# h2oiq_v4_long.net
KiCad netlist of a schematic drawn in EAGLE
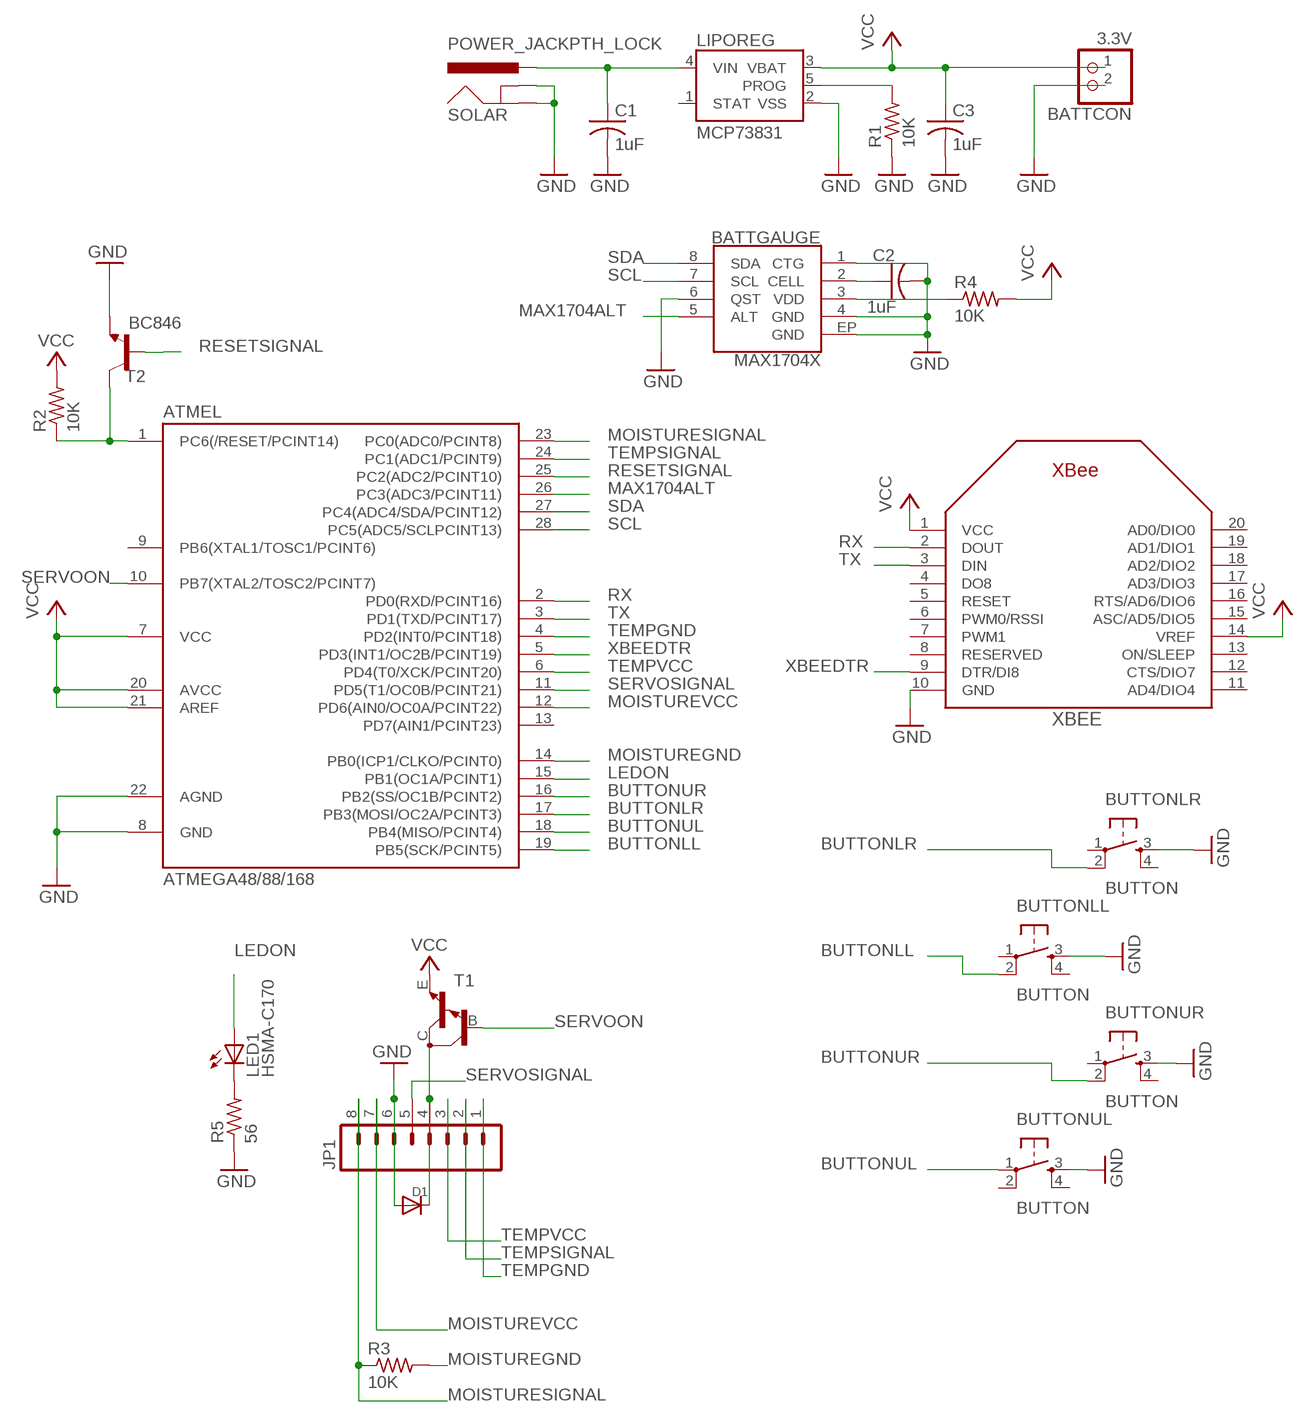
[diagram p0: schematic, sheet 1]

(export (version "E")
  (design (tool "Eeschema 10.0.6"))
  (components
    (comp (ref "ATMEL")
      (value "ATMEGA48/88/168")
      (footprint "eagle-import:DIL28-3")
      (libsource (lib "eagle-import") (part "MEGA48/88/168-PU"))
    )
    (comp (ref "BATTCON")
      (value "3.3V")
      (footprint "eagle-import:JST-PH-2-THM")
      (libsource (lib "eagle-import") (part "JST_2PIN-THM"))
    )
    (comp (ref "BATTGAUGE")
      (value "MAX1704X")
      (footprint "eagle-import:TDFN-8")
      (libsource (lib "eagle-import") (part "MAX1704X"))
    )
    (comp (ref "BUTTONLL")
      (value "BUTTON")
      (footprint "eagle-import:TACTILE-PTH")
      (libsource (lib "eagle-import") (part "TAC_SWITCHPTH"))
    )
    (comp (ref "BUTTONLR")
      (value "BUTTON")
      (footprint "eagle-import:TACTILE-PTH")
      (libsource (lib "eagle-import") (part "TAC_SWITCHPTH"))
    )
    (comp (ref "BUTTONUL")
      (value "BUTTON")
      (footprint "eagle-import:TACTILE-PTH")
      (libsource (lib "eagle-import") (part "TAC_SWITCHPTH"))
    )
    (comp (ref "BUTTONUR")
      (value "BUTTON")
      (footprint "eagle-import:TACTILE-PTH")
      (libsource (lib "eagle-import") (part "TAC_SWITCHPTH"))
    )
    (comp (ref "C1")
      (value "1uF")
      (footprint "eagle-import:C0603K")
      (libsource (lib "eagle-import") (part "C-USC0603K"))
    )
    (comp (ref "C2")
      (value "1uF")
      (footprint "eagle-import:C0603K")
      (libsource (lib "eagle-import") (part "C-USC0603K"))
    )
    (comp (ref "C3")
      (value "1uF")
      (footprint "eagle-import:C0603K")
      (libsource (lib "eagle-import") (part "C-USC0603K"))
    )
    (comp (ref "D1")
      (value "DIODESMA")
      (footprint "eagle-import:SMADIODE")
      (libsource (lib "eagle-import") (part "DIODESMA"))
    )
    (comp (ref "JP1")
      (value "M081X08")
      (footprint "eagle-import:1X08")
      (libsource (lib "eagle-import") (part "M081X08"))
    )
    (comp (ref "LED1")
      (value "HSMA-C170")
      (footprint "eagle-import:SMARTLED-TTW")
      (libsource (lib "eagle-import") (part "LED"))
    )
    (comp (ref "LIPOREG")
      (value "MCP73831")
      (footprint "eagle-import:SOT23-5")
      (libsource (lib "eagle-import") (part "MCP73831"))
    )
    (comp (ref "R1")
      (value "10K")
      (footprint "eagle-import:R0805")
      (libsource (lib "eagle-import") (part "R-US_R0805"))
    )
    (comp (ref "R2")
      (value "10K")
      (footprint "eagle-import:R0805")
      (libsource (lib "eagle-import") (part "R-US_R0805"))
    )
    (comp (ref "R3")
      (value "10K")
      (footprint "eagle-import:R0805")
      (libsource (lib "eagle-import") (part "R-US_R0805"))
    )
    (comp (ref "R4")
      (value "10K")
      (footprint "eagle-import:R0805")
      (libsource (lib "eagle-import") (part "R-US_R0805"))
    )
    (comp (ref "R5")
      (value "56")
      (footprint "eagle-import:R0805")
      (libsource (lib "eagle-import") (part "R-US_R0805"))
    )
    (comp (ref "SOLAR")
      (value "POWER_JACKPTH_LOCK")
      (footprint "eagle-import:POWER_JACK_PTH_LOCK")
      (libsource (lib "eagle-import") (part "POWER_JACKPTH_LOCK"))
    )
    (comp (ref "T1")
      (value "MMBTA13LT1-NPN_DARL-SOT23-BEC")
      (footprint "eagle-import:SOT23-BEC")
      (libsource (lib "eagle-import") (part "-NPN_DARL-SOT23-BECMMBTA13LT1"))
    )
    (comp (ref "T2")
      (value "BC846")
      (footprint "eagle-import:SOT23")
      (libsource (lib "eagle-import") (part "BC846"))
    )
    (comp (ref "XBEE")
      (value "XBEE")
      (footprint "eagle-import:XBEE")
      (libsource (lib "eagle-import") (part "XBEE"))
    )
  )
  (nets
    (net (code "1") (name "/BUTTONLL") (class "Default")
      (node (ref "ATMEL") (pin "19") (pinfunction "PB5(SCK/PCINT5)_19") (pintype "bidirectional"))
      (node (ref "BUTTONLL") (pin "2") (pinfunction "2_2") (pintype "passive"))
    )
    (net (code "2") (name "/BUTTONLR") (class "Default")
      (node (ref "ATMEL") (pin "17") (pinfunction "PB3(MOSI/OC2A/PCINT3)_17") (pintype "bidirectional"))
      (node (ref "BUTTONLR") (pin "2") (pinfunction "2_2") (pintype "passive"))
    )
    (net (code "3") (name "/BUTTONUL") (class "Default")
      (node (ref "ATMEL") (pin "18") (pinfunction "PB4(MISO/PCINT4)_18") (pintype "bidirectional"))
      (node (ref "BUTTONUL") (pin "1") (pinfunction "1_1") (pintype "passive"))
    )
    (net (code "4") (name "/BUTTONUR") (class "Default")
      (node (ref "ATMEL") (pin "16") (pinfunction "PB2(SS/OC1B/PCINT2)_16") (pintype "bidirectional"))
      (node (ref "BUTTONUR") (pin "2") (pinfunction "2_2") (pintype "passive"))
    )
    (net (code "5") (name "/LEDON") (class "Default")
      (node (ref "ATMEL") (pin "15") (pinfunction "PB1(OC1A/PCINT1)_15") (pintype "bidirectional"))
      (node (ref "LED1") (pin "A@1") (pinfunction "A_A@1") (pintype "passive"))
    )
    (net (code "6") (name "/MAX1704ALT") (class "Default")
      (node (ref "ATMEL") (pin "26") (pinfunction "PC3(ADC3/PCINT11)_26") (pintype "bidirectional"))
      (node (ref "BATTGAUGE") (pin "5") (pinfunction "ALT_5") (pintype "bidirectional"))
    )
    (net (code "7") (name "/MOISTUREGND") (class "Default")
      (node (ref "ATMEL") (pin "14") (pinfunction "PB0(ICP1/CLKO/PCINT0)_14") (pintype "bidirectional"))
      (node (ref "R3") (pin "2") (pinfunction "2_2") (pintype "passive"))
    )
    (net (code "8") (name "/MOISTURESIGNAL") (class "Default")
      (node (ref "ATMEL") (pin "23") (pinfunction "PC0(ADC0/PCINT8)_23") (pintype "bidirectional"))
      (node (ref "JP1") (pin "8") (pinfunction "8_8") (pintype "passive"))
      (node (ref "R3") (pin "1") (pinfunction "1_1") (pintype "passive"))
    )
    (net (code "9") (name "/MOISTUREVCC") (class "Default")
      (node (ref "ATMEL") (pin "12") (pinfunction "PD6(AIN0/OC0A/PCINT22)_12") (pintype "bidirectional"))
      (node (ref "JP1") (pin "7") (pinfunction "7_7") (pintype "passive"))
    )
    (net (code "10") (name "/RESETSIGNAL") (class "Default")
      (node (ref "ATMEL") (pin "25") (pinfunction "PC2(ADC2/PCINT10)_25") (pintype "bidirectional"))
      (node (ref "T2") (pin "1") (pinfunction "B_1") (pintype "passive"))
    )
    (net (code "11") (name "/RX") (class "Default")
      (node (ref "ATMEL") (pin "2") (pinfunction "PD0(RXD/PCINT16)_2") (pintype "bidirectional"))
      (node (ref "XBEE") (pin "2") (pinfunction "DOUT_2") (pintype "output"))
    )
    (net (code "12") (name "/SCL") (class "Default")
      (node (ref "ATMEL") (pin "28") (pinfunction "PC5(ADC5/SCLPCINT13)_28") (pintype "bidirectional"))
      (node (ref "BATTGAUGE") (pin "7") (pinfunction "SCL_7") (pintype "bidirectional"))
    )
    (net (code "13") (name "/SDA") (class "Default")
      (node (ref "ATMEL") (pin "27") (pinfunction "PC4(ADC4/SDA/PCINT12)_27") (pintype "bidirectional"))
      (node (ref "BATTGAUGE") (pin "8") (pinfunction "SDA_8") (pintype "bidirectional"))
    )
    (net (code "14") (name "/SERVOON") (class "Default")
      (node (ref "ATMEL") (pin "10") (pinfunction "PB7(XTAL2/TOSC2/PCINT7)_10") (pintype "bidirectional"))
      (node (ref "T1") (pin "B") (pinfunction "B_B") (pintype "passive"))
    )
    (net (code "15") (name "/SERVOSIGNAL") (class "Default")
      (node (ref "ATMEL") (pin "11") (pinfunction "PD5(T1/OC0B/PCINT21)_11") (pintype "bidirectional"))
      (node (ref "JP1") (pin "5") (pinfunction "5_5") (pintype "passive"))
    )
    (net (code "16") (name "/TEMPGND") (class "Default")
      (node (ref "ATMEL") (pin "4") (pinfunction "PD2(INT0/PCINT18)_4") (pintype "bidirectional"))
      (node (ref "JP1") (pin "1") (pinfunction "1_1") (pintype "passive"))
    )
    (net (code "17") (name "/TEMPSIGNAL") (class "Default")
      (node (ref "ATMEL") (pin "24") (pinfunction "PC1(ADC1/PCINT9)_24") (pintype "bidirectional"))
      (node (ref "JP1") (pin "2") (pinfunction "2_2") (pintype "passive"))
    )
    (net (code "18") (name "/TEMPVCC") (class "Default")
      (node (ref "ATMEL") (pin "6") (pinfunction "PD4(T0/XCK/PCINT20)_6") (pintype "bidirectional"))
      (node (ref "JP1") (pin "3") (pinfunction "3_3") (pintype "passive"))
    )
    (net (code "19") (name "/TX") (class "Default")
      (node (ref "ATMEL") (pin "3") (pinfunction "PD1(TXD/PCINT17)_3") (pintype "bidirectional"))
      (node (ref "XBEE") (pin "3") (pinfunction "DIN_3") (pintype "input"))
    )
    (net (code "20") (name "/XBEEDTR") (class "Default")
      (node (ref "ATMEL") (pin "5") (pinfunction "PD3(INT1/OC2B/PCINT19)_5") (pintype "bidirectional"))
      (node (ref "XBEE") (pin "9") (pinfunction "DTR/DI8_9") (pintype "input"))
    )
    (net (code "21") (name "GND") (class "Default")
      (node (ref "ATMEL") (pin "22") (pinfunction "AGND_22") (pintype "power_in"))
      (node (ref "ATMEL") (pin "8") (pinfunction "GND_8") (pintype "power_in"))
      (node (ref "BATTCON") (pin "2") (pinfunction "1_2") (pintype "passive"))
      (node (ref "BATTGAUGE") (pin "1") (pinfunction "CTG_1") (pintype "bidirectional"))
      (node (ref "BATTGAUGE") (pin "4") (pinfunction "GND_4") (pintype "bidirectional"))
      (node (ref "BATTGAUGE") (pin "6") (pinfunction "QST_6") (pintype "bidirectional"))
      (node (ref "BATTGAUGE") (pin "EP") (pinfunction "GND_EP") (pintype "bidirectional"))
      (node (ref "BUTTONLL") (pin "3") (pinfunction "3_3") (pintype "passive"))
      (node (ref "BUTTONLR") (pin "3") (pinfunction "3_3") (pintype "passive"))
      (node (ref "BUTTONUL") (pin "3") (pinfunction "3_3") (pintype "passive"))
      (node (ref "BUTTONUR") (pin "3") (pinfunction "3_3") (pintype "passive"))
      (node (ref "C1") (pin "2") (pinfunction "2_2") (pintype "passive"))
      (node (ref "C2") (pin "2") (pinfunction "2_2") (pintype "passive"))
      (node (ref "C3") (pin "2") (pinfunction "2_2") (pintype "passive"))
      (node (ref "D1") (pin "A") (pinfunction "A_A") (pintype "passive"))
      (node (ref "JP1") (pin "6") (pinfunction "6_6") (pintype "passive"))
      (node (ref "LIPOREG") (pin "2") (pinfunction "VSS_2") (pintype "power_in"))
      (node (ref "R1") (pin "1") (pinfunction "1_1") (pintype "passive"))
      (node (ref "R5") (pin "1") (pinfunction "1_1") (pintype "passive"))
      (node (ref "SOLAR") (pin "GND") (pinfunction "GND_GND") (pintype "bidirectional"))
      (node (ref "SOLAR") (pin "GNDBREAK") (pinfunction "GNDBREAK_GNDBREAK") (pintype "bidirectional"))
      (node (ref "T2") (pin "2") (pinfunction "E_2") (pintype "passive"))
      (node (ref "XBEE") (pin "10") (pinfunction "GND_10") (pintype "power_in"))
    )
    (net (code "22") (name "Net-(ATMEL-PC6({slash}RESET{slash}PCINT14))") (class "Default")
      (node (ref "ATMEL") (pin "1") (pinfunction "PC6(/RESET/PCINT14)_1") (pintype "bidirectional"))
      (node (ref "R2") (pin "1") (pinfunction "1_1") (pintype "passive"))
      (node (ref "T2") (pin "3") (pinfunction "C_3") (pintype "passive"))
    )
    (net (code "23") (name "Net-(BATTGAUGE-CELL)") (class "Default")
      (node (ref "BATTGAUGE") (pin "2") (pinfunction "CELL_2") (pintype "bidirectional"))
      (node (ref "C2") (pin "1") (pinfunction "1_1") (pintype "passive"))
    )
    (net (code "24") (name "Net-(BATTGAUGE-VDD)") (class "Default")
      (node (ref "BATTGAUGE") (pin "3") (pinfunction "VDD_3") (pintype "bidirectional"))
      (node (ref "R4") (pin "1") (pinfunction "1_1") (pintype "passive"))
    )
    (net (code "25") (name "Net-(D1-PadC)") (class "Default")
      (node (ref "D1") (pin "C") (pinfunction "C_C") (pintype "passive"))
      (node (ref "JP1") (pin "4") (pinfunction "4_4") (pintype "passive"))
      (node (ref "T1") (pin "C") (pinfunction "C_C") (pintype "passive"))
    )
    (net (code "26") (name "Net-(LED1-C)") (class "Default")
      (node (ref "LED1") (pin "C@1") (pinfunction "C_C@1") (pintype "passive"))
      (node (ref "R5") (pin "2") (pinfunction "2_2") (pintype "passive"))
    )
    (net (code "27") (name "Net-(LIPOREG-PROG)") (class "Default")
      (node (ref "LIPOREG") (pin "5") (pinfunction "PROG_5") (pintype "input"))
      (node (ref "R1") (pin "2") (pinfunction "2_2") (pintype "passive"))
    )
    (net (code "28") (name "Net-(LIPOREG-VIN)") (class "Default")
      (node (ref "C1") (pin "1") (pinfunction "1_1") (pintype "passive"))
      (node (ref "LIPOREG") (pin "4") (pinfunction "VIN_4") (pintype "power_in"))
      (node (ref "SOLAR") (pin "PWR") (pinfunction "PWR_PWR") (pintype "bidirectional"))
    )
    (net (code "29") (name "VCC") (class "Default")
      (node (ref "ATMEL") (pin "20") (pinfunction "AVCC_20") (pintype "passive"))
      (node (ref "ATMEL") (pin "21") (pinfunction "AREF_21") (pintype "passive"))
      (node (ref "ATMEL") (pin "7") (pinfunction "VCC_7") (pintype "power_in"))
      (node (ref "BATTCON") (pin "1") (pinfunction "2_1") (pintype "passive"))
      (node (ref "C3") (pin "1") (pinfunction "1_1") (pintype "passive"))
      (node (ref "LIPOREG") (pin "3") (pinfunction "VBAT_3") (pintype "power_in"))
      (node (ref "R2") (pin "2") (pinfunction "2_2") (pintype "passive"))
      (node (ref "R4") (pin "2") (pinfunction "2_2") (pintype "passive"))
      (node (ref "T1") (pin "E") (pinfunction "E_E") (pintype "passive"))
      (node (ref "XBEE") (pin "1") (pinfunction "VCC_1") (pintype "power_in"))
      (node (ref "XBEE") (pin "14") (pinfunction "VREF_14") (pintype "input"))
    )
    (net (code "30") (name "unconnected-(ATMEL-PB6(XTAL1{slash}TOSC1{slash}PCINT6)-Pad9)") (class "Default")
      (node (ref "ATMEL") (pin "9") (pinfunction "PB6(XTAL1/TOSC1/PCINT6)_9") (pintype "bidirectional"))
    )
    (net (code "31") (name "unconnected-(ATMEL-PD7(AIN1{slash}PCINT23)-Pad13)") (class "Default")
      (node (ref "ATMEL") (pin "13") (pinfunction "PD7(AIN1/PCINT23)_13") (pintype "bidirectional"))
    )
    (net (code "32") (name "unconnected-(BUTTONLL-Pad1)") (class "Default")
      (node (ref "BUTTONLL") (pin "1") (pinfunction "1_1") (pintype "passive"))
    )
    (net (code "33") (name "unconnected-(BUTTONLL-Pad4)") (class "Default")
      (node (ref "BUTTONLL") (pin "4") (pinfunction "4_4") (pintype "passive"))
    )
    (net (code "34") (name "unconnected-(BUTTONLR-Pad1)") (class "Default")
      (node (ref "BUTTONLR") (pin "1") (pinfunction "1_1") (pintype "passive"))
    )
    (net (code "35") (name "unconnected-(BUTTONLR-Pad4)") (class "Default")
      (node (ref "BUTTONLR") (pin "4") (pinfunction "4_4") (pintype "passive"))
    )
    (net (code "36") (name "unconnected-(BUTTONUL-Pad2)") (class "Default")
      (node (ref "BUTTONUL") (pin "2") (pinfunction "2_2") (pintype "passive"))
    )
    (net (code "37") (name "unconnected-(BUTTONUL-Pad4)") (class "Default")
      (node (ref "BUTTONUL") (pin "4") (pinfunction "4_4") (pintype "passive"))
    )
    (net (code "38") (name "unconnected-(BUTTONUR-Pad1)") (class "Default")
      (node (ref "BUTTONUR") (pin "1") (pinfunction "1_1") (pintype "passive"))
    )
    (net (code "39") (name "unconnected-(BUTTONUR-Pad4)") (class "Default")
      (node (ref "BUTTONUR") (pin "4") (pinfunction "4_4") (pintype "passive"))
    )
    (net (code "40") (name "unconnected-(LIPOREG-STAT-Pad1)") (class "Default")
      (node (ref "LIPOREG") (pin "1") (pinfunction "STAT_1") (pintype "output"))
    )
    (net (code "41") (name "unconnected-(XBEE-AD0{slash}DIO0-Pad20)") (class "Default")
      (node (ref "XBEE") (pin "20") (pinfunction "AD0/DIO0_20") (pintype "bidirectional"))
    )
    (net (code "42") (name "unconnected-(XBEE-AD1{slash}DIO1-Pad19)") (class "Default")
      (node (ref "XBEE") (pin "19") (pinfunction "AD1/DIO1_19") (pintype "bidirectional"))
    )
    (net (code "43") (name "unconnected-(XBEE-AD2{slash}DIO2-Pad18)") (class "Default")
      (node (ref "XBEE") (pin "18") (pinfunction "AD2/DIO2_18") (pintype "bidirectional"))
    )
    (net (code "44") (name "unconnected-(XBEE-AD3{slash}DIO3-Pad17)") (class "Default")
      (node (ref "XBEE") (pin "17") (pinfunction "AD3/DIO3_17") (pintype "bidirectional"))
    )
    (net (code "45") (name "unconnected-(XBEE-AD4{slash}DIO4-Pad11)") (class "Default")
      (node (ref "XBEE") (pin "11") (pinfunction "AD4/DIO4_11") (pintype "bidirectional"))
    )
    (net (code "46") (name "unconnected-(XBEE-ASC{slash}AD5{slash}DIO5-Pad15)") (class "Default")
      (node (ref "XBEE") (pin "15") (pinfunction "ASC/AD5/DIO5_15") (pintype "bidirectional"))
    )
    (net (code "47") (name "unconnected-(XBEE-CTS{slash}DIO7-Pad12)") (class "Default")
      (node (ref "XBEE") (pin "12") (pinfunction "CTS/DIO7_12") (pintype "bidirectional"))
    )
    (net (code "48") (name "unconnected-(XBEE-DO8-Pad4)") (class "Default")
      (node (ref "XBEE") (pin "4") (pinfunction "DO8_4") (pintype "output"))
    )
    (net (code "49") (name "unconnected-(XBEE-ON{slash}SLEEP-Pad13)") (class "Default")
      (node (ref "XBEE") (pin "13") (pinfunction "ON/SLEEP_13") (pintype "output"))
    )
    (net (code "50") (name "unconnected-(XBEE-PWM0{slash}RSSI-Pad6)") (class "Default")
      (node (ref "XBEE") (pin "6") (pinfunction "PWM0/RSSI_6") (pintype "output"))
    )
    (net (code "51") (name "unconnected-(XBEE-PWM1-Pad7)") (class "Default")
      (node (ref "XBEE") (pin "7") (pinfunction "PWM1_7") (pintype "output"))
    )
    (net (code "52") (name "unconnected-(XBEE-RESERVED-Pad8)") (class "Default")
      (node (ref "XBEE") (pin "8") (pinfunction "RESERVED_8") (pintype "no_connect"))
    )
    (net (code "53") (name "unconnected-(XBEE-RESET-Pad5)") (class "Default")
      (node (ref "XBEE") (pin "5") (pinfunction "RESET_5") (pintype "input"))
    )
    (net (code "54") (name "unconnected-(XBEE-RTS{slash}AD6{slash}DIO6-Pad16)") (class "Default")
      (node (ref "XBEE") (pin "16") (pinfunction "RTS/AD6/DIO6_16") (pintype "bidirectional"))
    )
  )
)
